# ESPixel.net
KiCad netlist of a schematic drawn in EAGLE
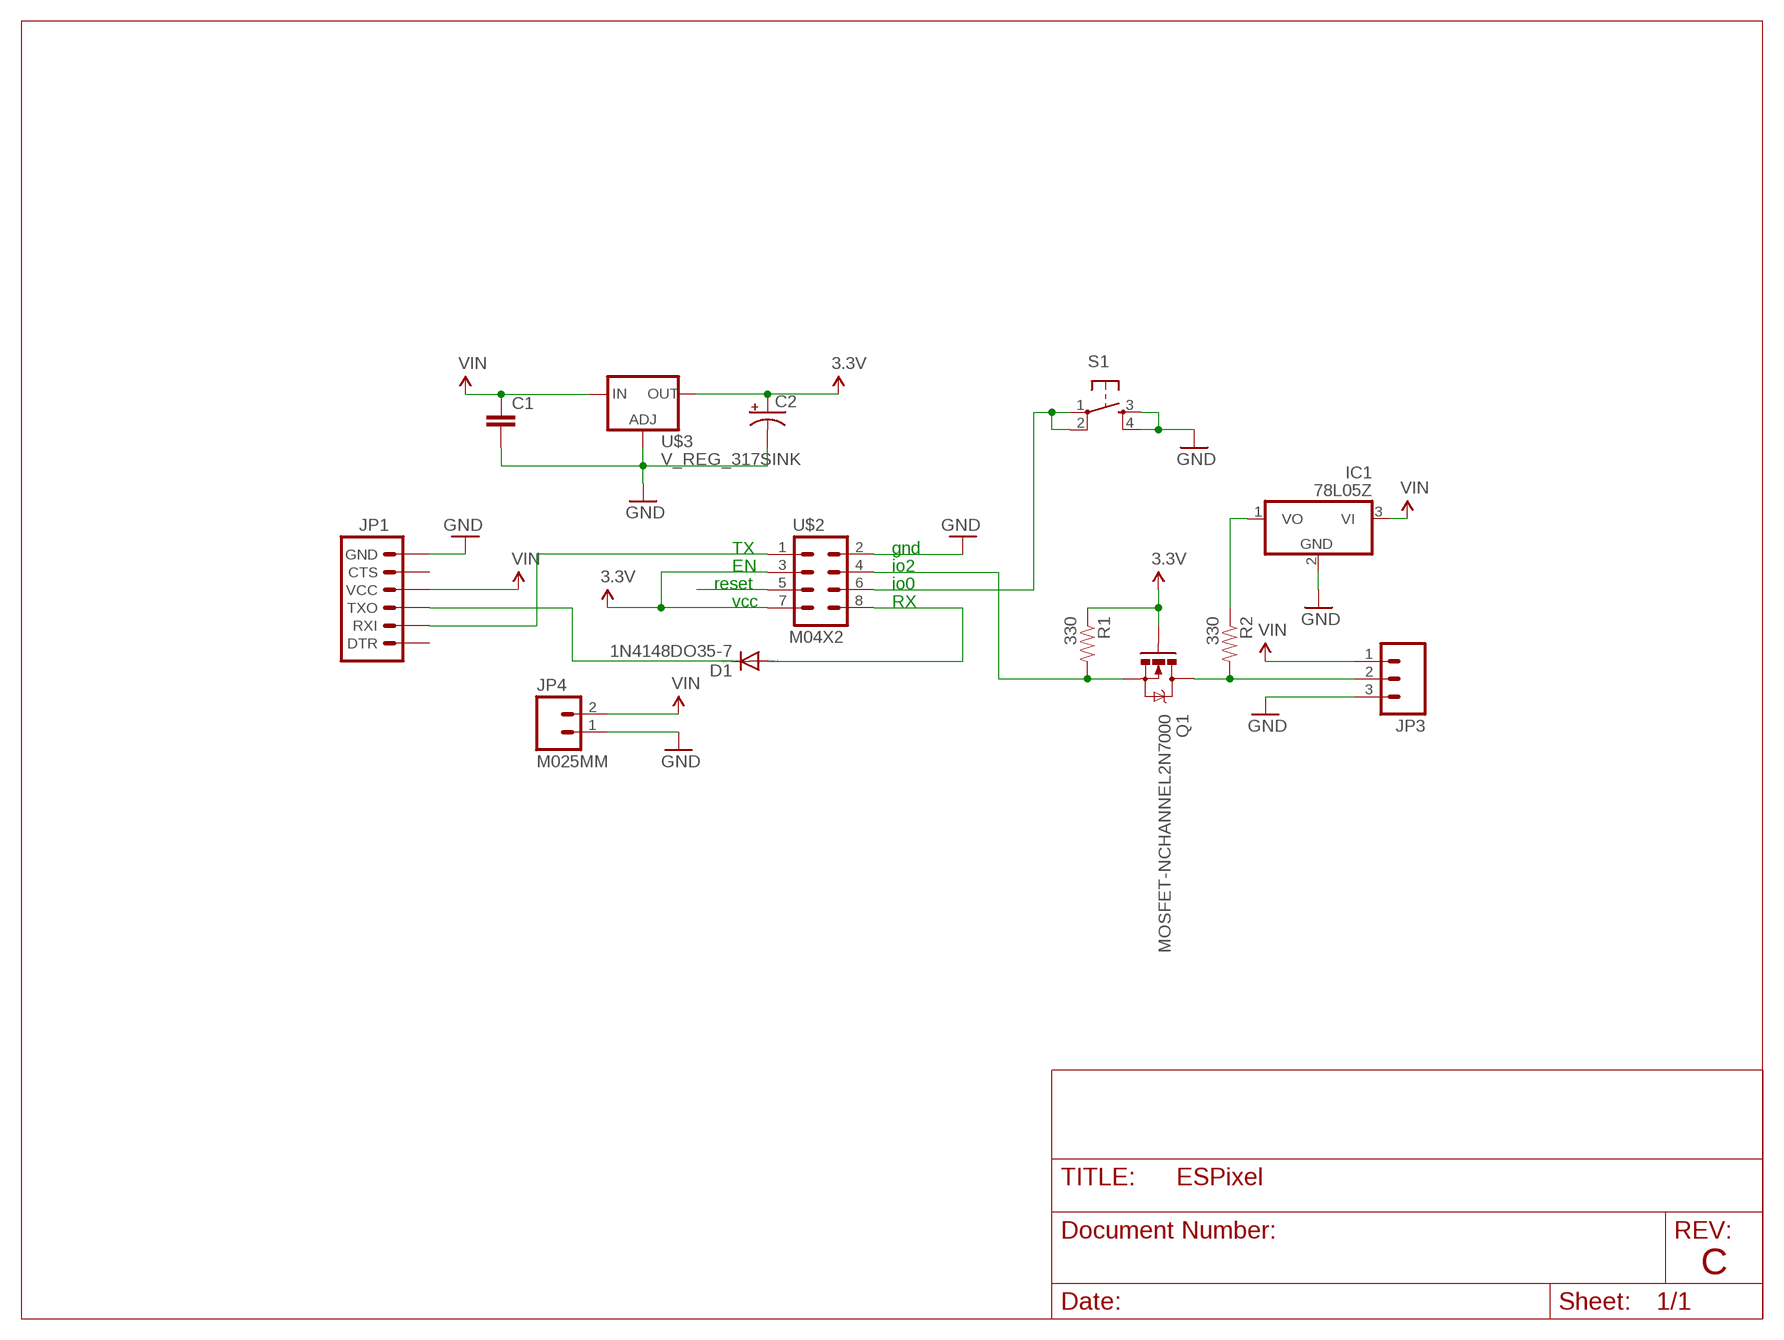
[diagram p0: schematic, sheet 1]

(export (version "E")
  (design (tool "Eeschema 10.0.6"))
  (components
    (comp (ref "C1")
      (value "CAPEZ")
      (footprint "eagle-import:CAP-PTH-SMALLEZ")
      (libsource (lib "eagle-import") (part "CAPEZ"))
    )
    (comp (ref "C2")
      (value "CAP_POLPTH2")
      (footprint "eagle-import:CPOL-RADIAL-10UF-25V")
      (libsource (lib "eagle-import") (part "CAP_POLPTH2"))
    )
    (comp (ref "D1")
      (value "1N4148DO35-7")
      (footprint "eagle-import:DO35-7")
      (libsource (lib "eagle-import") (part "1N4148DO35-7"))
    )
    (comp (ref "IC1")
      (value "78L05Z")
      (footprint "eagle-import:TO92")
      (libsource (lib "eagle-import") (part "78ZL05"))
    )
    (comp (ref "JP1")
      (value "ARDUINO_SERIAL_PROGRAMLOCK")
      (footprint "eagle-import:1X06_LOCK")
      (libsource (lib "eagle-import") (part "ARDUINO_SERIAL_PROGRAMLOCK"))
    )
    (comp (ref "JP3")
      (value "M03-SCREW-5MM")
      (footprint "eagle-import:SCREWTERMINAL-5MM-3")
      (libsource (lib "eagle-import") (part "M03-SCREW-5MM"))
    )
    (comp (ref "JP4")
      (value "M025MM")
      (footprint "eagle-import:SCREWTERMINAL-5MM-2")
      (libsource (lib "eagle-import") (part "M025MM"))
    )
    (comp (ref "Q1")
      (value "MOSFET-NCHANNEL2N7000")
      (footprint "eagle-import:TO-92")
      (libsource (lib "eagle-import") (part "MOSFET-NCHANNEL2N7000"))
    )
    (comp (ref "R1")
      (value "330")
      (footprint "eagle-import:AXIAL-0.3EZ")
      (libsource (lib "eagle-import") (part "RESISTOREZ"))
    )
    (comp (ref "R2")
      (value "330")
      (footprint "eagle-import:AXIAL-0.3EZ")
      (libsource (lib "eagle-import") (part "RESISTOREZ"))
    )
    (comp (ref "S1")
      (value "TAC_SWITCHPTH")
      (footprint "eagle-import:TACTILE-PTH")
      (libsource (lib "eagle-import") (part "TAC_SWITCHPTH"))
    )
    (comp (ref "U$2")
      (value "M04X2")
      (footprint "eagle-import:2X4")
      (libsource (lib "eagle-import") (part "M04X2"))
    )
    (comp (ref "U$3")
      (value "V_REG_317SINK")
      (footprint "eagle-import:TO220-ADJ")
      (libsource (lib "eagle-import") (part "V_REG_317SINK"))
    )
  )
  (nets
    (net (code "1") (name "3.3V") (class "Default")
      (node (ref "C2") (pin "1") (pinfunction "+_1") (pintype "passive"))
      (node (ref "Q1") (pin "2") (pinfunction "G_2") (pintype "passive"))
      (node (ref "R1") (pin "P$1") (pinfunction "1_P$1") (pintype "passive"))
      (node (ref "U$2") (pin "3") (pinfunction "3_3") (pintype "passive"))
      (node (ref "U$2") (pin "7") (pinfunction "7_7") (pintype "passive"))
      (node (ref "U$3") (pin "OUT") (pinfunction "OUT_OUT") (pintype "output"))
    )
    (net (code "2") (name "GND") (class "Default")
      (node (ref "C1") (pin "2") (pinfunction "2_2") (pintype "passive"))
      (node (ref "C2") (pin "2") (pinfunction "-_2") (pintype "passive"))
      (node (ref "IC1") (pin "2") (pinfunction "GND_2") (pintype "passive"))
      (node (ref "JP1") (pin "6") (pinfunction "GND_6") (pintype "passive"))
      (node (ref "JP3") (pin "3") (pinfunction "3_3") (pintype "passive"))
      (node (ref "JP4") (pin "1") (pinfunction "1_1") (pintype "passive"))
      (node (ref "S1") (pin "3") (pinfunction "3_3") (pintype "passive"))
      (node (ref "S1") (pin "4") (pinfunction "4_4") (pintype "passive"))
      (node (ref "U$2") (pin "2") (pinfunction "2_2") (pintype "passive"))
      (node (ref "U$3") (pin "ADJ") (pinfunction "ADJ_ADJ") (pintype "input"))
    )
    (net (code "3") (name "Net-(D1-PadA)") (class "Default")
      (node (ref "D1") (pin "A") (pinfunction "A_A") (pintype "passive"))
      (node (ref "U$2") (pin "8") (pinfunction "8_8") (pintype "passive"))
    )
    (net (code "4") (name "Net-(IC1-VO)") (class "Default")
      (node (ref "IC1") (pin "1") (pinfunction "VO_1") (pintype "passive"))
      (node (ref "R2") (pin "P$1") (pinfunction "1_P$1") (pintype "passive"))
    )
    (net (code "5") (name "Net-(JP1-RXI)") (class "Default")
      (node (ref "JP1") (pin "2") (pinfunction "RXI_2") (pintype "passive"))
      (node (ref "U$2") (pin "1") (pinfunction "1_1") (pintype "passive"))
    )
    (net (code "6") (name "Net-(JP1-TXO)") (class "Default")
      (node (ref "D1") (pin "C") (pinfunction "C_C") (pintype "passive"))
      (node (ref "JP1") (pin "3") (pinfunction "TXO_3") (pintype "passive"))
    )
    (net (code "7") (name "Net-(Q1-D)") (class "Default")
      (node (ref "JP3") (pin "2") (pinfunction "2_2") (pintype "passive"))
      (node (ref "Q1") (pin "3") (pinfunction "D_3") (pintype "passive"))
      (node (ref "R2") (pin "P$2") (pinfunction "2_P$2") (pintype "passive"))
    )
    (net (code "8") (name "Net-(Q1-S)") (class "Default")
      (node (ref "Q1") (pin "1") (pinfunction "S_1") (pintype "passive"))
      (node (ref "R1") (pin "P$2") (pinfunction "2_P$2") (pintype "passive"))
      (node (ref "U$2") (pin "4") (pinfunction "4_4") (pintype "passive"))
    )
    (net (code "9") (name "Net-(S1-Pad1)") (class "Default")
      (node (ref "S1") (pin "1") (pinfunction "1_1") (pintype "passive"))
      (node (ref "S1") (pin "2") (pinfunction "2_2") (pintype "passive"))
      (node (ref "U$2") (pin "6") (pinfunction "6_6") (pintype "passive"))
    )
    (net (code "10") (name "VIN") (class "Default")
      (node (ref "C1") (pin "1") (pinfunction "1_1") (pintype "passive"))
      (node (ref "IC1") (pin "3") (pinfunction "VI_3") (pintype "input"))
      (node (ref "JP1") (pin "4") (pinfunction "VCC_4") (pintype "passive"))
      (node (ref "JP3") (pin "1") (pinfunction "1_1") (pintype "passive"))
      (node (ref "JP4") (pin "2") (pinfunction "2_2") (pintype "passive"))
      (node (ref "U$3") (pin "IN") (pinfunction "IN_IN") (pintype "input"))
    )
    (net (code "11") (name "unconnected-(JP1-CTS-Pad5)") (class "Default")
      (node (ref "JP1") (pin "5") (pinfunction "CTS_5") (pintype "passive"))
    )
    (net (code "12") (name "unconnected-(JP1-DTR-Pad1)") (class "Default")
      (node (ref "JP1") (pin "1") (pinfunction "DTR_1") (pintype "passive"))
    )
    (net (code "13") (name "unconnected-(U$2-Pad5)") (class "Default")
      (node (ref "U$2") (pin "5") (pinfunction "5_5") (pintype "passive"))
    )
  )
)
